# PROTOCOL_PART.net
KiCad netlist of a schematic drawn in Altium Designer
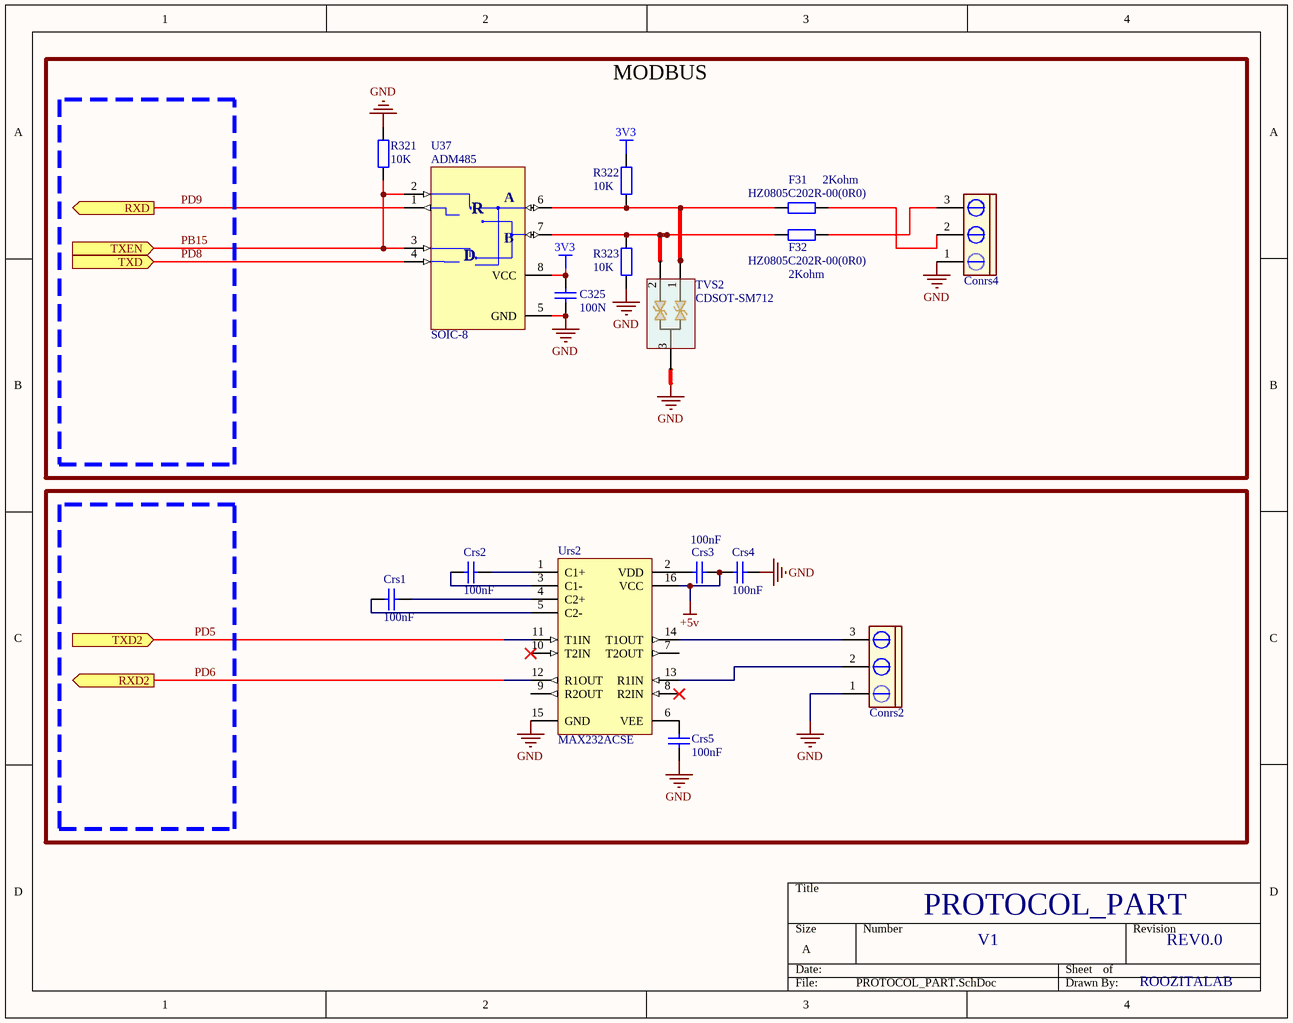
[diagram p0: PROTOCOL_PART.SchDoc]

(export (version "E")
  (design (tool "Eeschema 10.0.6"))
  (components
    (comp (ref "C325")
      (value "100N")
      (footprint "0805.")
      (description "Capacitor")
      (fields
        (field (name "MANUFACTURER") "Generic Components")
        (field (name "PUBLISHER") "Altium Hobart Technology Centre")
      )
      (libsource (lib "Miscellaneous Devices") (part "Cap"))
    )
    (comp (ref "Conrs2")
      (value "CON3 pin Green")
      (footprint "My_CN3")
      (description "Connector green screw")
      (libsource (lib "Mylib") (part "CON3 pin Green"))
    )
    (comp (ref "Conrs4")
      (value "CON3 pin Green")
      (footprint "My_CN3")
      (description "Connector green screw")
      (libsource (lib "Mylib") (part "CON3 pin Green"))
    )
    (comp (ref "Crs1")
      (value "100nF")
      (footprint "CAP 1206 (3216X08L)")
      (description "Capacitor")
      (fields (field (name "Comment") "Cap") (field (name "PUBLISHER") "Altium Limited"))
      (libsource (lib "Miscellaneous Devices") (part "Cap"))
    )
    (comp (ref "Crs2")
      (value "100nF")
      (footprint "CAP 1206 (3216X08L)")
      (description "Capacitor")
      (fields (field (name "Comment") "Cap") (field (name "PUBLISHER") "Altium Limited"))
      (libsource (lib "Miscellaneous Devices") (part "Cap"))
    )
    (comp (ref "Crs3")
      (value "100nF")
      (footprint "CAP 1206 (3216X08L)")
      (description "Capacitor")
      (fields (field (name "Comment") "Cap") (field (name "PUBLISHER") "Altium Limited"))
      (libsource (lib "Miscellaneous Devices") (part "Cap"))
    )
    (comp (ref "Crs4")
      (value "100nF")
      (footprint "CAP 1206 (3216X08L)")
      (description "Capacitor")
      (fields (field (name "Comment") "Cap") (field (name "PUBLISHER") "Altium Limited"))
      (libsource (lib "Miscellaneous Devices") (part "Cap"))
    )
    (comp (ref "Crs5")
      (value "100nF")
      (footprint "CAP 1206 (3216X08L)")
      (description "Capacitor")
      (fields (field (name "Comment") "Cap") (field (name "PUBLISHER") "Altium Limited"))
      (libsource (lib "Miscellaneous Devices") (part "Cap"))
    )
    (comp (ref "F31")
      (value "HZ0805C202R-00(0R0)")
      (footprint "0805.")
      (description "Resistor")
      (fields (field (name "PUBLISHER") "Altium Limited"))
      (libsource (lib "Miscellaneous Devices") (part "Res2"))
    )
    (comp (ref "F32")
      (value "HZ0805C202R-00(0R0)")
      (footprint "0805.")
      (description "Resistor")
      (fields (field (name "PUBLISHER") "Altium Limited"))
      (libsource (lib "Miscellaneous Devices") (part "Res2"))
    )
    (comp (ref "R321")
      (value "10K")
      (footprint "0805.")
      (description "Resistor")
      (fields
        (field (name "MANUFACTURER") "Generic Components")
        (field (name "PUBLISHER") "Altium Hobart Technology Centre")
      )
      (libsource (lib "") (part "Res2_1"))
    )
    (comp (ref "R322")
      (value "10K")
      (footprint "0805.")
      (description "Resistor")
      (fields
        (field (name "MANUFACTURER") "Generic Components")
        (field (name "PUBLISHER") "Altium Hobart Technology Centre")
      )
      (libsource (lib "") (part "Res2_1"))
    )
    (comp (ref "R323")
      (value "10K")
      (footprint "0805.")
      (description "Resistor")
      (fields
        (field (name "MANUFACTURER") "Generic Components")
        (field (name "PUBLISHER") "Altium Hobart Technology Centre")
      )
      (libsource (lib "") (part "Res2_1"))
    )
    (comp (ref "TVS2")
      (value "CDSOT-SM712")
      (footprint "2N3906_SMD")
      (libsource (lib "my schem") (part "nup2105"))
    )
    (comp (ref "U37")
      (value "ADM485")
      (footprint "SOIC8")
      (description "Low-Power, Slew-Rate-Limited RS-485/RS-422 Transceiver")
      (fields
        (field (name "MANUFACTURER") "Maxim")
        (field (name "PUBLISHER") "Altium Hobart Technology Centre")
      )
      (libsource (lib "sensor1") (part "MAX485EPA"))
    )
    (comp (ref "Urs2")
      (value "MAX232ACSE")
      (footprint "SOIC16")
      (description "+5V Powered, Multi-Channel RS-232 Driver/Receiver")
      (fields (field (name "PUBLISHER") "Altium Limited"))
      (libsource (lib "Maxim Communication Transceiver") (part "MAX232ACSE"))
    )
  )
  (nets
    (net (code "1") (name "+5v") (class "Default")
      (node (ref "Crs3") (pin "1") (pinfunction "1_1") (pintype "passive"))
      (node (ref "Crs4") (pin "2") (pinfunction "2_2") (pintype "passive"))
      (node (ref "Urs2") (pin "16") (pinfunction "VCC_16") (pintype "power_in"))
    )
    (net (code "2") (name "/PB15") (class "Default")
      (node (ref "R321") (pin "2") (pinfunction "2_2") (pintype "passive"))
      (node (ref "U37") (pin "2") (pinfunction "~{RE}_2") (pintype "input"))
      (node (ref "U37") (pin "3") (pinfunction "DE_3") (pintype "input"))
    )
    (net (code "3") (name "/PD5") (class "Default")
      (node (ref "Urs2") (pin "11") (pinfunction "T1IN_11") (pintype "input"))
    )
    (net (code "4") (name "/PD6") (class "Default")
      (node (ref "Urs2") (pin "12") (pinfunction "R1OUT_12") (pintype "output"))
    )
    (net (code "5") (name "/PD8") (class "Default")
      (node (ref "U37") (pin "4") (pinfunction "DI_4") (pintype "input"))
    )
    (net (code "6") (name "/PD9") (class "Default")
      (node (ref "U37") (pin "1") (pinfunction "RO_1") (pintype "output"))
    )
    (net (code "7") (name "3V3") (class "Default")
      (node (ref "C325") (pin "2") (pinfunction "2_2") (pintype "passive"))
      (node (ref "R322") (pin "1") (pinfunction "1_1") (pintype "passive"))
      (node (ref "U37") (pin "8") (pinfunction "VCC_8") (pintype "power_in"))
    )
    (net (code "8") (name "GND") (class "Default")
      (node (ref "C325") (pin "1") (pinfunction "1_1") (pintype "passive"))
      (node (ref "Conrs2") (pin "1") (pinfunction "1_1") (pintype "passive"))
      (node (ref "Conrs4") (pin "1") (pinfunction "1_1") (pintype "passive"))
      (node (ref "Crs4") (pin "1") (pinfunction "1_1") (pintype "passive"))
      (node (ref "Crs5") (pin "1") (pinfunction "1_1") (pintype "passive"))
      (node (ref "R321") (pin "1") (pinfunction "1_1") (pintype "passive"))
      (node (ref "R323") (pin "2") (pinfunction "2_2") (pintype "passive"))
      (node (ref "TVS2") (pin "3") (pinfunction "3_3") (pintype "passive"))
      (node (ref "U37") (pin "5") (pinfunction "GND_5") (pintype "power_in"))
      (node (ref "Urs2") (pin "15") (pinfunction "GND_15") (pintype "power_in"))
    )
    (net (code "9") (name "Net-(Conrs4-Pad2)") (class "Default")
      (node (ref "Conrs4") (pin "2") (pinfunction "2_2") (pintype "passive"))
      (node (ref "F31") (pin "2") (pinfunction "2_2") (pintype "passive"))
    )
    (net (code "10") (name "Net-(Conrs4-Pad3)") (class "Default")
      (node (ref "Conrs4") (pin "3") (pinfunction "3_3") (pintype "passive"))
      (node (ref "F32") (pin "2") (pinfunction "2_2") (pintype "passive"))
    )
    (net (code "11") (name "Net-(U37-A)") (class "Default")
      (node (ref "F31") (pin "1") (pinfunction "1_1") (pintype "passive"))
      (node (ref "R322") (pin "2") (pinfunction "2_2") (pintype "passive"))
      (node (ref "TVS2") (pin "1") (pinfunction "1_1") (pintype "passive"))
      (node (ref "U37") (pin "6") (pinfunction "A_6") (pintype "bidirectional"))
    )
    (net (code "12") (name "Net-(U37-B)") (class "Default")
      (node (ref "F32") (pin "1") (pinfunction "1_1") (pintype "passive"))
      (node (ref "R323") (pin "1") (pinfunction "1_1") (pintype "passive"))
      (node (ref "TVS2") (pin "2") (pinfunction "2_2") (pintype "passive"))
      (node (ref "U37") (pin "7") (pinfunction "B_7") (pintype "bidirectional"))
    )
    (net (code "13") (name "Net-(Urs2-C1+)") (class "Default")
      (node (ref "Crs2") (pin "1") (pinfunction "1_1") (pintype "passive"))
      (node (ref "Urs2") (pin "1") (pinfunction "C1+_1") (pintype "passive"))
    )
    (net (code "14") (name "Net-(Urs2-C1-)") (class "Default")
      (node (ref "Crs2") (pin "2") (pinfunction "2_2") (pintype "passive"))
      (node (ref "Urs2") (pin "3") (pinfunction "C1-_3") (pintype "passive"))
    )
    (net (code "15") (name "Net-(Urs2-C2+)") (class "Default")
      (node (ref "Crs1") (pin "2") (pinfunction "2_2") (pintype "passive"))
      (node (ref "Urs2") (pin "4") (pinfunction "C2+_4") (pintype "passive"))
    )
    (net (code "16") (name "Net-(Urs2-C2-)") (class "Default")
      (node (ref "Crs1") (pin "1") (pinfunction "1_1") (pintype "passive"))
      (node (ref "Urs2") (pin "5") (pinfunction "C2-_5") (pintype "passive"))
    )
    (net (code "17") (name "Net-(Urs2-R1IN)") (class "Default")
      (node (ref "Conrs2") (pin "2") (pinfunction "2_2") (pintype "passive"))
      (node (ref "Urs2") (pin "13") (pinfunction "R1IN_13") (pintype "input"))
    )
    (net (code "18") (name "Net-(Urs2-T1OUT)") (class "Default")
      (node (ref "Conrs2") (pin "3") (pinfunction "3_3") (pintype "passive"))
      (node (ref "Urs2") (pin "14") (pinfunction "T1OUT_14") (pintype "output"))
    )
    (net (code "19") (name "Net-(Urs2-VDD)") (class "Default")
      (node (ref "Crs3") (pin "2") (pinfunction "2_2") (pintype "passive"))
      (node (ref "Urs2") (pin "2") (pinfunction "VDD_2") (pintype "power_in"))
    )
    (net (code "20") (name "Net-(Urs2-VEE)") (class "Default")
      (node (ref "Crs5") (pin "2") (pinfunction "2_2") (pintype "passive"))
      (node (ref "Urs2") (pin "6") (pinfunction "VEE_6") (pintype "power_in"))
    )
    (net (code "21") (name "unconnected-(Urs2-R2IN-Pad8)") (class "Default")
      (node (ref "Urs2") (pin "8") (pinfunction "R2IN_8") (pintype "input+no_connect"))
    )
    (net (code "22") (name "unconnected-(Urs2-R2OUT-Pad9)") (class "Default")
      (node (ref "Urs2") (pin "9") (pinfunction "R2OUT_9") (pintype "output"))
    )
    (net (code "23") (name "unconnected-(Urs2-T2IN-Pad10)") (class "Default")
      (node (ref "Urs2") (pin "10") (pinfunction "T2IN_10") (pintype "input+no_connect"))
    )
    (net (code "24") (name "unconnected-(Urs2-T2OUT-Pad7)") (class "Default")
      (node (ref "Urs2") (pin "7") (pinfunction "T2OUT_7") (pintype "output"))
    )
  )
)
